# Audio.net
KiCad netlist of a schematic drawn in Altium Designer
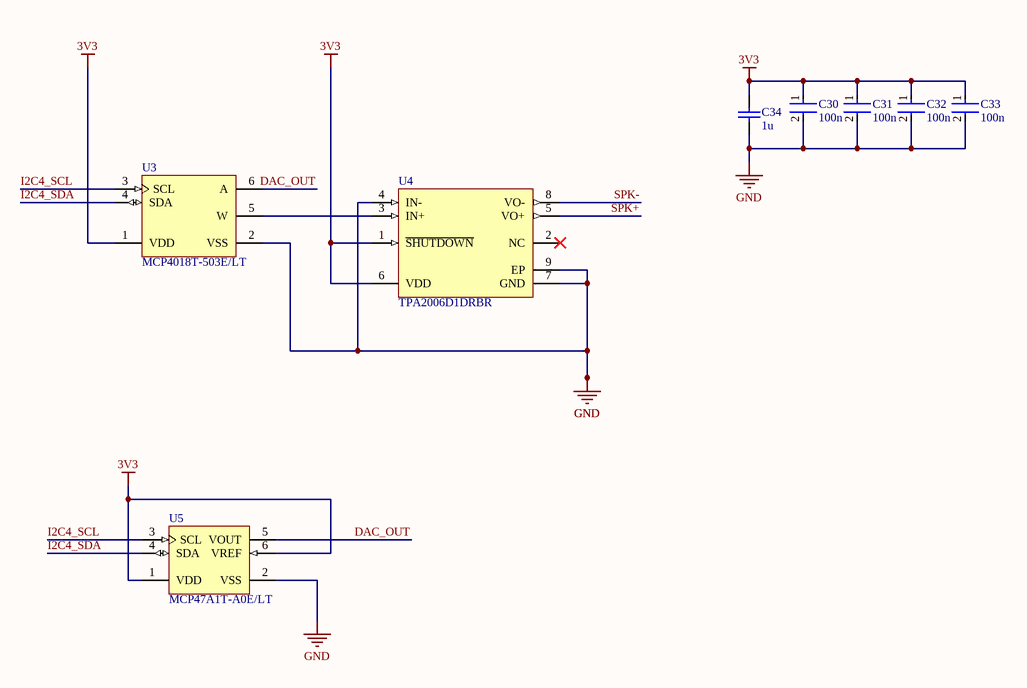
[diagram p0: Audio.SchDoc]

(export (version "E")
  (design (tool "Eeschema 10.0.6"))
  (components
    (comp (ref "C30")
      (value "100n")
      (footprint "FP-GRM188-0_1-e0_2_0_55-IPC_A")
      (description "Chip Multilayer Ceramic Capacitors for General Purpose, 0603, 10uF, X5R, 15%, 20%, 6.3V")
      (fields (field (name "VOLTAGE") "6.3V") (field (name "TOLERANCE") "20%"))
      (libsource (lib "Altium Content Vault") (part "02cd4be3c70576c341d710602a673aa"))
    )
    (comp (ref "C31")
      (value "100n")
      (footprint "FP-GRM188-0_1-e0_2_0_55-IPC_A")
      (description "Chip Multilayer Ceramic Capacitors for General Purpose, 0603, 10uF, X5R, 15%, 20%, 6.3V")
      (fields (field (name "VOLTAGE") "6.3V") (field (name "TOLERANCE") "20%"))
      (libsource (lib "Altium Content Vault") (part "02cd4be3c70576c341d710602a673aa"))
    )
    (comp (ref "C32")
      (value "100n")
      (footprint "FP-GRM188-0_1-e0_2_0_55-IPC_A")
      (description "Chip Multilayer Ceramic Capacitors for General Purpose, 0603, 10uF, X5R, 15%, 20%, 6.3V")
      (fields (field (name "VOLTAGE") "6.3V") (field (name "TOLERANCE") "20%"))
      (libsource (lib "Altium Content Vault") (part "02cd4be3c70576c341d710602a673aa"))
    )
    (comp (ref "C33")
      (value "100n")
      (footprint "FP-GRM188-0_1-e0_2_0_55-IPC_A")
      (description "Chip Multilayer Ceramic Capacitors for General Purpose, 0603, 10uF, X5R, 15%, 20%, 6.3V")
      (fields (field (name "VOLTAGE") "6.3V") (field (name "TOLERANCE") "20%"))
      (libsource (lib "Altium Content Vault") (part "02cd4be3c70576c341d710602a673aa"))
    )
    (comp (ref "C34")
      (value "1u")
      (footprint "CAPC2013X135X45LL10T25")
      (description "Chip Capacitor, 4.7 uF, +/- 10%, 16 V, -55 to 85 degC, 0805 (2012 Metric), RoHS, Tape and Reel")
      (fields (field (name "TOLERANCE") "10%") (field (name "PARTNUMBER") "GRM21BR61C475KA88L"))
      (libsource (lib "Altium Content Vault") (part "CAP-NP-2"))
    )
    (comp (ref "U3")
      (value "MCP4018T-503E/LT")
      (footprint "SC70-LT6_N")
      (description "7-Bit Single I2C Digital POT with Volatile Memory, 6-pin SC70, Extended Temperature, Tape and Reel")
      (libsource (lib "Altium Content Vault") (part "IN-DPOT-MCP4018-6"))
    )
    (comp (ref "U4")
      (value "TPA2006D1DRBR")
      (footprint "DRB0008A_V")
      (fields (field (name "MANUFACTURER") "Texas Instruments"))
      (libsource (lib "Altium Content Vault") (part "TI-TPA2005_6D1XDXX8-TP"))
    )
    (comp (ref "U5")
      (value "MCP47A1T-A0E/LT")
      (footprint "MCHP-SC70-LT6_N")
      (fields (field (name "MANUFACTURER") "Microchip"))
      (libsource (lib "Altium Content Vault") (part "MCHP-MCP47XA1-XXXXX-6"))
    )
  )
  (nets
    (net (code "1") (name "/DAC_OUT") (class "Default")
      (node (ref "U3") (pin "6") (pinfunction "A_6") (pintype "passive"))
      (node (ref "U5") (pin "5") (pinfunction "VOUT_5") (pintype "power_in"))
    )
    (net (code "2") (name "/I2C4_SCL") (class "Default")
      (node (ref "U3") (pin "3") (pinfunction "SCL_3") (pintype "input"))
      (node (ref "U5") (pin "3") (pinfunction "SCL_3") (pintype "input"))
    )
    (net (code "3") (name "/I2C4_SDA") (class "Default")
      (node (ref "U3") (pin "4") (pinfunction "SDA_4") (pintype "bidirectional"))
      (node (ref "U5") (pin "4") (pinfunction "SDA_4") (pintype "bidirectional"))
    )
    (net (code "4") (name "/SPK+") (class "Default")
      (node (ref "U4") (pin "5") (pinfunction "VO+_5") (pintype "output"))
    )
    (net (code "5") (name "/SPK-") (class "Default")
      (node (ref "U4") (pin "8") (pinfunction "VO-_8") (pintype "output"))
    )
    (net (code "6") (name "3V3") (class "Default")
      (node (ref "C30") (pin "1") (pinfunction "1_1") (pintype "passive"))
      (node (ref "C31") (pin "1") (pinfunction "1_1") (pintype "passive"))
      (node (ref "C32") (pin "1") (pinfunction "1_1") (pintype "passive"))
      (node (ref "C33") (pin "1") (pinfunction "1_1") (pintype "passive"))
      (node (ref "C34") (pin "2") (pinfunction "2_2") (pintype "passive"))
      (node (ref "U3") (pin "1") (pinfunction "VDD_1") (pintype "power_in"))
      (node (ref "U4") (pin "1") (pinfunction "~{SHUTDOWN}_1") (pintype "input"))
      (node (ref "U4") (pin "6") (pinfunction "VDD_6") (pintype "power_in"))
      (node (ref "U5") (pin "1") (pinfunction "VDD_1") (pintype "power_in"))
      (node (ref "U5") (pin "6") (pinfunction "VREF_6") (pintype "input"))
    )
    (net (code "7") (name "GND") (class "Default")
      (node (ref "C30") (pin "2") (pinfunction "2_2") (pintype "passive"))
      (node (ref "C31") (pin "2") (pinfunction "2_2") (pintype "passive"))
      (node (ref "C32") (pin "2") (pinfunction "2_2") (pintype "passive"))
      (node (ref "C33") (pin "2") (pinfunction "2_2") (pintype "passive"))
      (node (ref "C34") (pin "1") (pinfunction "1_1") (pintype "passive"))
      (node (ref "U3") (pin "2") (pinfunction "VSS_2") (pintype "power_in"))
      (node (ref "U4") (pin "4") (pinfunction "IN-_4") (pintype "input"))
      (node (ref "U4") (pin "7") (pinfunction "GND_7") (pintype "power_in"))
      (node (ref "U4") (pin "9") (pinfunction "EP_9") (pintype "power_in"))
      (node (ref "U5") (pin "2") (pinfunction "VSS_2") (pintype "power_in"))
    )
    (net (code "8") (name "Net-(U3-W)") (class "Default")
      (node (ref "U3") (pin "5") (pinfunction "W_5") (pintype "passive"))
      (node (ref "U4") (pin "3") (pinfunction "IN+_3") (pintype "input"))
    )
    (net (code "9") (name "unconnected-(U4-NC-Pad2)") (class "Default")
      (node (ref "U4") (pin "2") (pinfunction "NC_2") (pintype "passive+no_connect"))
    )
  )
)
